# PulseBeeper.net
KiCad netlist of a schematic drawn in Altium Designer
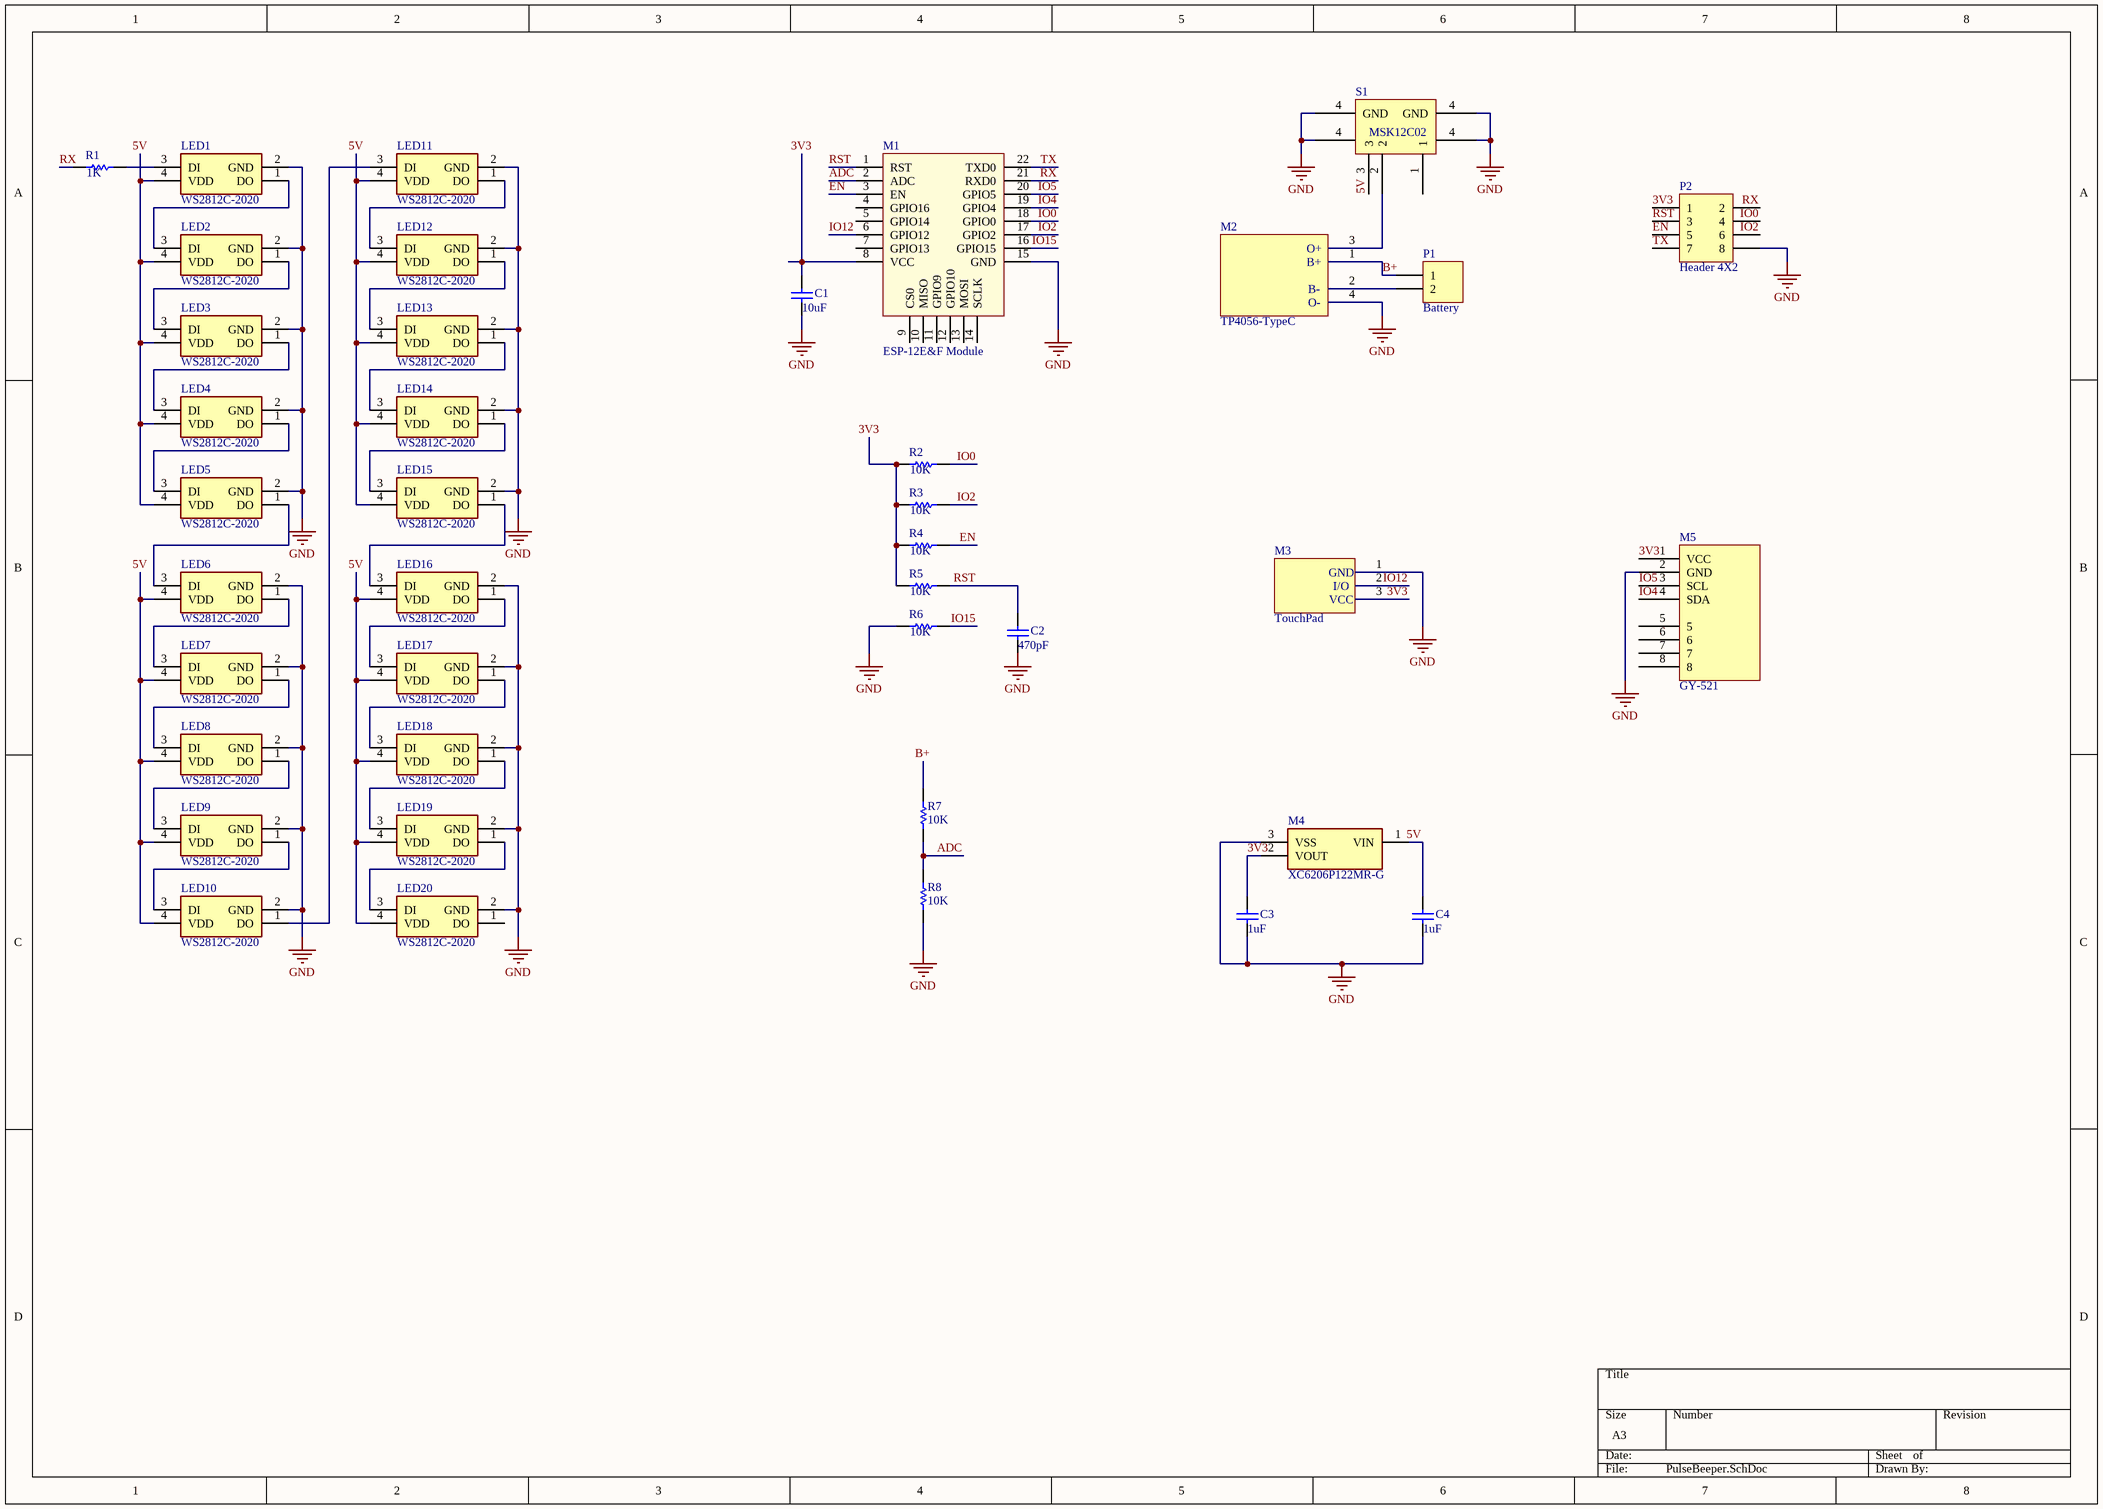
[diagram p0: PulseBeeper.SchDoc]

(export (version "E")
  (design (tool "Eeschema 10.0.6"))
  (components
    (comp (ref "C1")
      (value "10uF")
      (footprint "6-0805_N")
      (description "Capacitor")
      (fields (field (name "Comment") "Cap") (field (name "PUBLISHER") "Altium Limited"))
      (libsource (lib "Miscellaneous Devices") (part "Cap"))
    )
    (comp (ref "C2")
      (value "470pF")
      (footprint "6-0805_N")
      (description "Capacitor")
      (fields (field (name "Comment") "Cap") (field (name "PUBLISHER") "Altium Limited"))
      (libsource (lib "Miscellaneous Devices") (part "Cap"))
    )
    (comp (ref "C3")
      (value "1uF")
      (footprint "6-0805_N")
      (description "Capacitor")
      (fields (field (name "Comment") "Cap") (field (name "PUBLISHER") "Altium Limited"))
      (libsource (lib "Miscellaneous Devices") (part "Cap"))
    )
    (comp (ref "C4")
      (value "1uF")
      (footprint "6-0805_N")
      (description "Capacitor")
      (fields (field (name "Comment") "Cap") (field (name "PUBLISHER") "Altium Limited"))
      (libsource (lib "Miscellaneous Devices") (part "Cap"))
    )
    (comp (ref "LED1")
      (value "WS2812C-2020")
      (footprint "WS2812 3535")
      (description "LED")
      (libsource (lib "PulseBeeper") (part "WS2812C-2020"))
    )
    (comp (ref "LED2")
      (value "WS2812C-2020")
      (footprint "WS2812 3535")
      (description "LED")
      (libsource (lib "PulseBeeper") (part "WS2812C-2020"))
    )
    (comp (ref "LED3")
      (value "WS2812C-2020")
      (footprint "WS2812 3535")
      (description "LED")
      (libsource (lib "PulseBeeper") (part "WS2812C-2020"))
    )
    (comp (ref "LED4")
      (value "WS2812C-2020")
      (footprint "WS2812 3535")
      (description "LED")
      (libsource (lib "PulseBeeper") (part "WS2812C-2020"))
    )
    (comp (ref "LED5")
      (value "WS2812C-2020")
      (footprint "WS2812 3535")
      (description "LED")
      (libsource (lib "PulseBeeper") (part "WS2812C-2020"))
    )
    (comp (ref "LED6")
      (value "WS2812C-2020")
      (footprint "WS2812 3535")
      (description "LED")
      (libsource (lib "PulseBeeper") (part "WS2812C-2020"))
    )
    (comp (ref "LED7")
      (value "WS2812C-2020")
      (footprint "WS2812 3535")
      (description "LED")
      (libsource (lib "PulseBeeper") (part "WS2812C-2020"))
    )
    (comp (ref "LED8")
      (value "WS2812C-2020")
      (footprint "WS2812 3535")
      (description "LED")
      (libsource (lib "PulseBeeper") (part "WS2812C-2020"))
    )
    (comp (ref "LED9")
      (value "WS2812C-2020")
      (footprint "WS2812 3535")
      (description "LED")
      (libsource (lib "PulseBeeper") (part "WS2812C-2020"))
    )
    (comp (ref "LED10")
      (value "WS2812C-2020")
      (footprint "WS2812 3535")
      (description "LED")
      (libsource (lib "PulseBeeper") (part "WS2812C-2020"))
    )
    (comp (ref "LED11")
      (value "WS2812C-2020")
      (footprint "WS2812 3535")
      (description "LED")
      (libsource (lib "PulseBeeper") (part "WS2812C-2020"))
    )
    (comp (ref "LED12")
      (value "WS2812C-2020")
      (footprint "WS2812 3535")
      (description "LED")
      (libsource (lib "PulseBeeper") (part "WS2812C-2020"))
    )
    (comp (ref "LED13")
      (value "WS2812C-2020")
      (footprint "WS2812 3535")
      (description "LED")
      (libsource (lib "PulseBeeper") (part "WS2812C-2020"))
    )
    (comp (ref "LED14")
      (value "WS2812C-2020")
      (footprint "WS2812 3535")
      (description "LED")
      (libsource (lib "PulseBeeper") (part "WS2812C-2020"))
    )
    (comp (ref "LED15")
      (value "WS2812C-2020")
      (footprint "WS2812 3535")
      (description "LED")
      (libsource (lib "PulseBeeper") (part "WS2812C-2020"))
    )
    (comp (ref "LED16")
      (value "WS2812C-2020")
      (footprint "WS2812 3535")
      (description "LED")
      (libsource (lib "PulseBeeper") (part "WS2812C-2020"))
    )
    (comp (ref "LED17")
      (value "WS2812C-2020")
      (footprint "WS2812 3535")
      (description "LED")
      (libsource (lib "PulseBeeper") (part "WS2812C-2020"))
    )
    (comp (ref "LED18")
      (value "WS2812C-2020")
      (footprint "WS2812 3535")
      (description "LED")
      (libsource (lib "PulseBeeper") (part "WS2812C-2020"))
    )
    (comp (ref "LED19")
      (value "WS2812C-2020")
      (footprint "WS2812 3535")
      (description "LED")
      (libsource (lib "PulseBeeper") (part "WS2812C-2020"))
    )
    (comp (ref "LED20")
      (value "WS2812C-2020")
      (footprint "WS2812 3535")
      (description "LED")
      (libsource (lib "PulseBeeper") (part "WS2812C-2020"))
    )
    (comp (ref "M1")
      (value "ESP-12E&F Module")
      (footprint "ESP-12E&F Module")
      (libsource (lib "PulseBeeper") (part "ESP-12E&F Module"))
    )
    (comp (ref "M2")
      (value "TP4056-TypeC")
      (footprint "TP4056_17X26")
      (libsource (lib "PulseBeeper") (part "TP4056-TypeC"))
    )
    (comp (ref "M3")
      (value "TouchPad")
      (footprint "TouchPad")
      (libsource (lib "PulseBeeper") (part "TouchPad"))
    )
    (comp (ref "M4")
      (value "XC6206P122MR-G")
      (footprint "SOT23_N")
      (description "Integrated Circuit")
      (fields (field (name "MOUSER PART NUMBER") "865-XC6206P122MR-G"))
      (libsource (lib "PulseBeeper") (part "XC6206P122MR-G"))
    )
    (comp (ref "M5") (value "GY-521") (footprint "GY-521") (libsource (lib "PulseBeeper") (part "GY-521")))
    (comp (ref "P1")
      (value "Battery")
      (footprint "BatteryPad")
      (description "Header, 2-Pin")
      (fields (field (name "PUBLISHER") "Altium Limited"))
      (libsource (lib "Miscellaneous Connectors") (part "Header 2"))
    )
    (comp (ref "P2")
      (value "Header 4X2")
      (footprint "HDR2X4")
      (description "Header, 4-Pin, Dual row")
      (fields (field (name "PUBLISHER") "Altium Limited"))
      (libsource (lib "Miscellaneous Connectors") (part "Header 4X2"))
    )
    (comp (ref "R1")
      (value "1K")
      (footprint "6-0805_N")
      (description "Resistor")
      (fields (field (name "Comment") "Res1") (field (name "PUBLISHER") "Altium Limited"))
      (libsource (lib "Miscellaneous Devices") (part "Res1"))
    )
    (comp (ref "R2")
      (value "10K")
      (footprint "6-0805_N")
      (description "Resistor")
      (fields (field (name "Comment") "Res1") (field (name "PUBLISHER") "Altium Limited"))
      (libsource (lib "Miscellaneous Devices") (part "Res1"))
    )
    (comp (ref "R3")
      (value "10K")
      (footprint "6-0805_N")
      (description "Resistor")
      (fields (field (name "Comment") "Res1") (field (name "PUBLISHER") "Altium Limited"))
      (libsource (lib "Miscellaneous Devices") (part "Res1"))
    )
    (comp (ref "R4")
      (value "10K")
      (footprint "6-0805_N")
      (description "Resistor")
      (fields (field (name "Comment") "Res1") (field (name "PUBLISHER") "Altium Limited"))
      (libsource (lib "Miscellaneous Devices") (part "Res1"))
    )
    (comp (ref "R5")
      (value "10K")
      (footprint "6-0805_N")
      (description "Resistor")
      (fields (field (name "Comment") "Res1") (field (name "PUBLISHER") "Altium Limited"))
      (libsource (lib "Miscellaneous Devices") (part "Res1"))
    )
    (comp (ref "R6")
      (value "10K")
      (footprint "6-0805_N")
      (description "Resistor")
      (fields (field (name "Comment") "Res1") (field (name "PUBLISHER") "Altium Limited"))
      (libsource (lib "Miscellaneous Devices") (part "Res1"))
    )
    (comp (ref "R7")
      (value "10K")
      (footprint "6-0805_N")
      (description "Resistor")
      (fields (field (name "Comment") "Res1") (field (name "PUBLISHER") "Altium Limited"))
      (libsource (lib "Miscellaneous Devices") (part "Res1"))
    )
    (comp (ref "R8")
      (value "10K")
      (footprint "6-0805_N")
      (description "Resistor")
      (fields (field (name "Comment") "Res1") (field (name "PUBLISHER") "Altium Limited"))
      (libsource (lib "Miscellaneous Devices") (part "Res1"))
    )
    (comp (ref "S1")
      (value "MSK12C02")
      (footprint "MSK12C02")
      (libsource (lib "PulseBeeper") (part "MSK12C02"))
    )
  )
  (nets
    (net (code "1") (name "/3V3") (class "Default")
      (node (ref "C1") (pin "2") (pinfunction "2_2") (pintype "passive"))
      (node (ref "C3") (pin "2") (pinfunction "2_2") (pintype "passive"))
      (node (ref "M1") (pin "8") (pinfunction "VCC_8") (pintype "passive"))
      (node (ref "M3") (pin "3") (pinfunction "3_3") (pintype "passive"))
      (node (ref "M4") (pin "2") (pinfunction "VOUT_2") (pintype "passive"))
      (node (ref "M5") (pin "1") (pinfunction "VCC_1") (pintype "passive"))
      (node (ref "P2") (pin "1") (pinfunction "1_1") (pintype "passive"))
      (node (ref "R2") (pin "1") (pinfunction "1_1") (pintype "passive"))
      (node (ref "R3") (pin "1") (pinfunction "1_1") (pintype "passive"))
      (node (ref "R4") (pin "1") (pinfunction "1_1") (pintype "passive"))
      (node (ref "R5") (pin "1") (pinfunction "1_1") (pintype "passive"))
    )
    (net (code "2") (name "/5V") (class "Default")
      (node (ref "C4") (pin "2") (pinfunction "2_2") (pintype "passive"))
      (node (ref "LED1") (pin "4") (pinfunction "VDD_4") (pintype "passive"))
      (node (ref "LED10") (pin "4") (pinfunction "VDD_4") (pintype "passive"))
      (node (ref "LED11") (pin "4") (pinfunction "VDD_4") (pintype "passive"))
      (node (ref "LED12") (pin "4") (pinfunction "VDD_4") (pintype "passive"))
      (node (ref "LED13") (pin "4") (pinfunction "VDD_4") (pintype "passive"))
      (node (ref "LED14") (pin "4") (pinfunction "VDD_4") (pintype "passive"))
      (node (ref "LED15") (pin "4") (pinfunction "VDD_4") (pintype "passive"))
      (node (ref "LED16") (pin "4") (pinfunction "VDD_4") (pintype "passive"))
      (node (ref "LED17") (pin "4") (pinfunction "VDD_4") (pintype "passive"))
      (node (ref "LED18") (pin "4") (pinfunction "VDD_4") (pintype "passive"))
      (node (ref "LED19") (pin "4") (pinfunction "VDD_4") (pintype "passive"))
      (node (ref "LED2") (pin "4") (pinfunction "VDD_4") (pintype "passive"))
      (node (ref "LED20") (pin "4") (pinfunction "VDD_4") (pintype "passive"))
      (node (ref "LED3") (pin "4") (pinfunction "VDD_4") (pintype "passive"))
      (node (ref "LED4") (pin "4") (pinfunction "VDD_4") (pintype "passive"))
      (node (ref "LED5") (pin "4") (pinfunction "VDD_4") (pintype "passive"))
      (node (ref "LED6") (pin "4") (pinfunction "VDD_4") (pintype "passive"))
      (node (ref "LED7") (pin "4") (pinfunction "VDD_4") (pintype "passive"))
      (node (ref "LED8") (pin "4") (pinfunction "VDD_4") (pintype "passive"))
      (node (ref "LED9") (pin "4") (pinfunction "VDD_4") (pintype "passive"))
      (node (ref "M4") (pin "1") (pinfunction "VIN_1") (pintype "passive"))
      (node (ref "S1") (pin "3") (pinfunction "3_3") (pintype "passive"))
    )
    (net (code "3") (name "/ADC") (class "Default")
      (node (ref "M1") (pin "2") (pinfunction "ADC_2") (pintype "passive"))
      (node (ref "R7") (pin "1") (pinfunction "1_1") (pintype "passive"))
      (node (ref "R8") (pin "2") (pinfunction "2_2") (pintype "passive"))
    )
    (net (code "4") (name "/B+") (class "Default")
      (node (ref "M2") (pin "1") (pinfunction "1_1") (pintype "passive"))
      (node (ref "P1") (pin "1") (pinfunction "1_1") (pintype "passive"))
      (node (ref "R7") (pin "2") (pinfunction "2_2") (pintype "passive"))
    )
    (net (code "5") (name "/EN") (class "Default")
      (node (ref "M1") (pin "3") (pinfunction "EN_3") (pintype "passive"))
      (node (ref "P2") (pin "5") (pinfunction "5_5") (pintype "passive"))
      (node (ref "R4") (pin "2") (pinfunction "2_2") (pintype "passive"))
    )
    (net (code "6") (name "/IO0") (class "Default")
      (node (ref "M1") (pin "18") (pinfunction "GPIO0_18") (pintype "passive"))
      (node (ref "P2") (pin "4") (pinfunction "4_4") (pintype "passive"))
      (node (ref "R2") (pin "2") (pinfunction "2_2") (pintype "passive"))
    )
    (net (code "7") (name "/IO2") (class "Default")
      (node (ref "M1") (pin "17") (pinfunction "GPIO2_17") (pintype "passive"))
      (node (ref "P2") (pin "6") (pinfunction "6_6") (pintype "passive"))
      (node (ref "R3") (pin "2") (pinfunction "2_2") (pintype "passive"))
    )
    (net (code "8") (name "/IO4") (class "Default")
      (node (ref "M1") (pin "19") (pinfunction "GPIO4_19") (pintype "passive"))
      (node (ref "M5") (pin "4") (pinfunction "SDA_4") (pintype "passive"))
    )
    (net (code "9") (name "/IO5") (class "Default")
      (node (ref "M1") (pin "20") (pinfunction "GPIO5_20") (pintype "passive"))
      (node (ref "M5") (pin "3") (pinfunction "SCL_3") (pintype "passive"))
    )
    (net (code "10") (name "/IO12") (class "Default")
      (node (ref "M1") (pin "6") (pinfunction "GPIO12_6") (pintype "passive"))
      (node (ref "M3") (pin "2") (pinfunction "2_2") (pintype "passive"))
    )
    (net (code "11") (name "/IO15") (class "Default")
      (node (ref "M1") (pin "16") (pinfunction "GPIO15_16") (pintype "passive"))
      (node (ref "R6") (pin "2") (pinfunction "2_2") (pintype "passive"))
    )
    (net (code "12") (name "/RST") (class "Default")
      (node (ref "C2") (pin "2") (pinfunction "2_2") (pintype "passive"))
      (node (ref "M1") (pin "1") (pinfunction "RST_1") (pintype "passive"))
      (node (ref "P2") (pin "3") (pinfunction "3_3") (pintype "passive"))
      (node (ref "R5") (pin "2") (pinfunction "2_2") (pintype "passive"))
    )
    (net (code "13") (name "/RX") (class "Default")
      (node (ref "M1") (pin "21") (pinfunction "RXD0_21") (pintype "passive"))
      (node (ref "P2") (pin "2") (pinfunction "2_2") (pintype "passive"))
      (node (ref "R1") (pin "1") (pinfunction "1_1") (pintype "passive"))
    )
    (net (code "14") (name "/TX") (class "Default")
      (node (ref "M1") (pin "22") (pinfunction "TXD0_22") (pintype "passive"))
      (node (ref "P2") (pin "7") (pinfunction "7_7") (pintype "passive"))
    )
    (net (code "15") (name "GND") (class "Default")
      (node (ref "C1") (pin "1") (pinfunction "1_1") (pintype "passive"))
      (node (ref "C2") (pin "1") (pinfunction "1_1") (pintype "passive"))
      (node (ref "C3") (pin "1") (pinfunction "1_1") (pintype "passive"))
      (node (ref "C4") (pin "1") (pinfunction "1_1") (pintype "passive"))
      (node (ref "LED1") (pin "2") (pinfunction "GND_2") (pintype "passive"))
      (node (ref "LED10") (pin "2") (pinfunction "GND_2") (pintype "passive"))
      (node (ref "LED11") (pin "2") (pinfunction "GND_2") (pintype "passive"))
      (node (ref "LED12") (pin "2") (pinfunction "GND_2") (pintype "passive"))
      (node (ref "LED13") (pin "2") (pinfunction "GND_2") (pintype "passive"))
      (node (ref "LED14") (pin "2") (pinfunction "GND_2") (pintype "passive"))
      (node (ref "LED15") (pin "2") (pinfunction "GND_2") (pintype "passive"))
      (node (ref "LED16") (pin "2") (pinfunction "GND_2") (pintype "passive"))
      (node (ref "LED17") (pin "2") (pinfunction "GND_2") (pintype "passive"))
      (node (ref "LED18") (pin "2") (pinfunction "GND_2") (pintype "passive"))
      (node (ref "LED19") (pin "2") (pinfunction "GND_2") (pintype "passive"))
      (node (ref "LED2") (pin "2") (pinfunction "GND_2") (pintype "passive"))
      (node (ref "LED20") (pin "2") (pinfunction "GND_2") (pintype "passive"))
      (node (ref "LED3") (pin "2") (pinfunction "GND_2") (pintype "passive"))
      (node (ref "LED4") (pin "2") (pinfunction "GND_2") (pintype "passive"))
      (node (ref "LED5") (pin "2") (pinfunction "GND_2") (pintype "passive"))
      (node (ref "LED6") (pin "2") (pinfunction "GND_2") (pintype "passive"))
      (node (ref "LED7") (pin "2") (pinfunction "GND_2") (pintype "passive"))
      (node (ref "LED8") (pin "2") (pinfunction "GND_2") (pintype "passive"))
      (node (ref "LED9") (pin "2") (pinfunction "GND_2") (pintype "passive"))
      (node (ref "M1") (pin "15") (pinfunction "GND_15") (pintype "passive"))
      (node (ref "M2") (pin "4") (pinfunction "4_4") (pintype "passive"))
      (node (ref "M3") (pin "1") (pinfunction "1_1") (pintype "passive"))
      (node (ref "M4") (pin "3") (pinfunction "VSS_3") (pintype "passive"))
      (node (ref "M5") (pin "2") (pinfunction "GND_2") (pintype "passive"))
      (node (ref "P2") (pin "8") (pinfunction "8_8") (pintype "passive"))
      (node (ref "R6") (pin "1") (pinfunction "1_1") (pintype "passive"))
      (node (ref "R8") (pin "1") (pinfunction "1_1") (pintype "passive"))
      (node (ref "S1") (pin "4") (pinfunction "GND_4") (pintype "passive"))
    )
    (net (code "16") (name "Net-(LED1-DI)") (class "Default")
      (node (ref "LED1") (pin "3") (pinfunction "DI_3") (pintype "passive"))
      (node (ref "R1") (pin "2") (pinfunction "2_2") (pintype "passive"))
    )
    (net (code "17") (name "Net-(LED1-DO)") (class "Default")
      (node (ref "LED1") (pin "1") (pinfunction "DO_1") (pintype "passive"))
      (node (ref "LED2") (pin "3") (pinfunction "DI_3") (pintype "passive"))
    )
    (net (code "18") (name "Net-(LED2-DO)") (class "Default")
      (node (ref "LED2") (pin "1") (pinfunction "DO_1") (pintype "passive"))
      (node (ref "LED3") (pin "3") (pinfunction "DI_3") (pintype "passive"))
    )
    (net (code "19") (name "Net-(LED3-DO)") (class "Default")
      (node (ref "LED3") (pin "1") (pinfunction "DO_1") (pintype "passive"))
      (node (ref "LED4") (pin "3") (pinfunction "DI_3") (pintype "passive"))
    )
    (net (code "20") (name "Net-(LED4-DO)") (class "Default")
      (node (ref "LED4") (pin "1") (pinfunction "DO_1") (pintype "passive"))
      (node (ref "LED5") (pin "3") (pinfunction "DI_3") (pintype "passive"))
    )
    (net (code "21") (name "Net-(LED5-DO)") (class "Default")
      (node (ref "LED5") (pin "1") (pinfunction "DO_1") (pintype "passive"))
      (node (ref "LED6") (pin "3") (pinfunction "DI_3") (pintype "passive"))
    )
    (net (code "22") (name "Net-(LED6-DO)") (class "Default")
      (node (ref "LED6") (pin "1") (pinfunction "DO_1") (pintype "passive"))
      (node (ref "LED7") (pin "3") (pinfunction "DI_3") (pintype "passive"))
    )
    (net (code "23") (name "Net-(LED7-DO)") (class "Default")
      (node (ref "LED7") (pin "1") (pinfunction "DO_1") (pintype "passive"))
      (node (ref "LED8") (pin "3") (pinfunction "DI_3") (pintype "passive"))
    )
    (net (code "24") (name "Net-(LED8-DO)") (class "Default")
      (node (ref "LED8") (pin "1") (pinfunction "DO_1") (pintype "passive"))
      (node (ref "LED9") (pin "3") (pinfunction "DI_3") (pintype "passive"))
    )
    (net (code "25") (name "Net-(LED10-DI)") (class "Default")
      (node (ref "LED10") (pin "3") (pinfunction "DI_3") (pintype "passive"))
      (node (ref "LED9") (pin "1") (pinfunction "DO_1") (pintype "passive"))
    )
    (net (code "26") (name "Net-(LED10-DO)") (class "Default")
      (node (ref "LED10") (pin "1") (pinfunction "DO_1") (pintype "passive"))
      (node (ref "LED11") (pin "3") (pinfunction "DI_3") (pintype "passive"))
    )
    (net (code "27") (name "Net-(LED11-DO)") (class "Default")
      (node (ref "LED11") (pin "1") (pinfunction "DO_1") (pintype "passive"))
      (node (ref "LED12") (pin "3") (pinfunction "DI_3") (pintype "passive"))
    )
    (net (code "28") (name "Net-(LED12-DO)") (class "Default")
      (node (ref "LED12") (pin "1") (pinfunction "DO_1") (pintype "passive"))
      (node (ref "LED13") (pin "3") (pinfunction "DI_3") (pintype "passive"))
    )
    (net (code "29") (name "Net-(LED13-DO)") (class "Default")
      (node (ref "LED13") (pin "1") (pinfunction "DO_1") (pintype "passive"))
      (node (ref "LED14") (pin "3") (pinfunction "DI_3") (pintype "passive"))
    )
    (net (code "30") (name "Net-(LED14-DO)") (class "Default")
      (node (ref "LED14") (pin "1") (pinfunction "DO_1") (pintype "passive"))
      (node (ref "LED15") (pin "3") (pinfunction "DI_3") (pintype "passive"))
    )
    (net (code "31") (name "Net-(LED15-DO)") (class "Default")
      (node (ref "LED15") (pin "1") (pinfunction "DO_1") (pintype "passive"))
      (node (ref "LED16") (pin "3") (pinfunction "DI_3") (pintype "passive"))
    )
    (net (code "32") (name "Net-(LED16-DO)") (class "Default")
      (node (ref "LED16") (pin "1") (pinfunction "DO_1") (pintype "passive"))
      (node (ref "LED17") (pin "3") (pinfunction "DI_3") (pintype "passive"))
    )
    (net (code "33") (name "Net-(LED17-DO)") (class "Default")
      (node (ref "LED17") (pin "1") (pinfunction "DO_1") (pintype "passive"))
      (node (ref "LED18") (pin "3") (pinfunction "DI_3") (pintype "passive"))
    )
    (net (code "34") (name "Net-(LED18-DO)") (class "Default")
      (node (ref "LED18") (pin "1") (pinfunction "DO_1") (pintype "passive"))
      (node (ref "LED19") (pin "3") (pinfunction "DI_3") (pintype "passive"))
    )
    (net (code "35") (name "Net-(LED19-DO)") (class "Default")
      (node (ref "LED19") (pin "1") (pinfunction "DO_1") (pintype "passive"))
      (node (ref "LED20") (pin "3") (pinfunction "DI_3") (pintype "passive"))
    )
    (net (code "36") (name "Net-(M2-Pad2)") (class "Default")
      (node (ref "M2") (pin "2") (pinfunction "2_2") (pintype "passive"))
      (node (ref "P1") (pin "2") (pinfunction "2_2") (pintype "passive"))
    )
    (net (code "37") (name "Net-(M2-Pad3)") (class "Default")
      (node (ref "M2") (pin "3") (pinfunction "3_3") (pintype "passive"))
      (node (ref "S1") (pin "2") (pinfunction "2_2") (pintype "passive"))
    )
    (net (code "38") (name "unconnected-(LED20-DO-Pad1)") (class "Default")
      (node (ref "LED20") (pin "1") (pinfunction "DO_1") (pintype "passive"))
    )
    (net (code "39") (name "unconnected-(M1-CS0-Pad9)") (class "Default")
      (node (ref "M1") (pin "9") (pinfunction "CS0_9") (pintype "passive"))
    )
    (net (code "40") (name "unconnected-(M1-GPIO9-Pad11)") (class "Default")
      (node (ref "M1") (pin "11") (pinfunction "GPIO9_11") (pintype "passive"))
    )
    (net (code "41") (name "unconnected-(M1-GPIO10-Pad12)") (class "Default")
      (node (ref "M1") (pin "12") (pinfunction "GPIO10_12") (pintype "passive"))
    )
    (net (code "42") (name "unconnected-(M1-GPIO13-Pad7)") (class "Default")
      (node (ref "M1") (pin "7") (pinfunction "GPIO13_7") (pintype "passive"))
    )
    (net (code "43") (name "unconnected-(M1-GPIO14-Pad5)") (class "Default")
      (node (ref "M1") (pin "5") (pinfunction "GPIO14_5") (pintype "passive"))
    )
    (net (code "44") (name "unconnected-(M1-GPIO16-Pad4)") (class "Default")
      (node (ref "M1") (pin "4") (pinfunction "GPIO16_4") (pintype "passive"))
    )
    (net (code "45") (name "unconnected-(M1-MISO-Pad10)") (class "Default")
      (node (ref "M1") (pin "10") (pinfunction "MISO_10") (pintype "passive"))
    )
    (net (code "46") (name "unconnected-(M1-MOSI-Pad13)") (class "Default")
      (node (ref "M1") (pin "13") (pinfunction "MOSI_13") (pintype "passive"))
    )
    (net (code "47") (name "unconnected-(M1-SCLK-Pad14)") (class "Default")
      (node (ref "M1") (pin "14") (pinfunction "SCLK_14") (pintype "passive"))
    )
    (net (code "48") (name "unconnected-(M5-Pad5)") (class "Default")
      (node (ref "M5") (pin "5") (pinfunction "5_5") (pintype "passive"))
    )
    (net (code "49") (name "unconnected-(M5-Pad6)") (class "Default")
      (node (ref "M5") (pin "6") (pinfunction "6_6") (pintype "passive"))
    )
    (net (code "50") (name "unconnected-(M5-Pad7)") (class "Default")
      (node (ref "M5") (pin "7") (pinfunction "7_7") (pintype "passive"))
    )
    (net (code "51") (name "unconnected-(M5-Pad8)") (class "Default")
      (node (ref "M5") (pin "8") (pinfunction "8_8") (pintype "passive"))
    )
    (net (code "52") (name "unconnected-(S1-Pad1)") (class "Default")
      (node (ref "S1") (pin "1") (pinfunction "1_1") (pintype "passive"))
    )
  )
)
